# SwitchDemoFeather.net
KiCad netlist of a schematic drawn in EAGLE
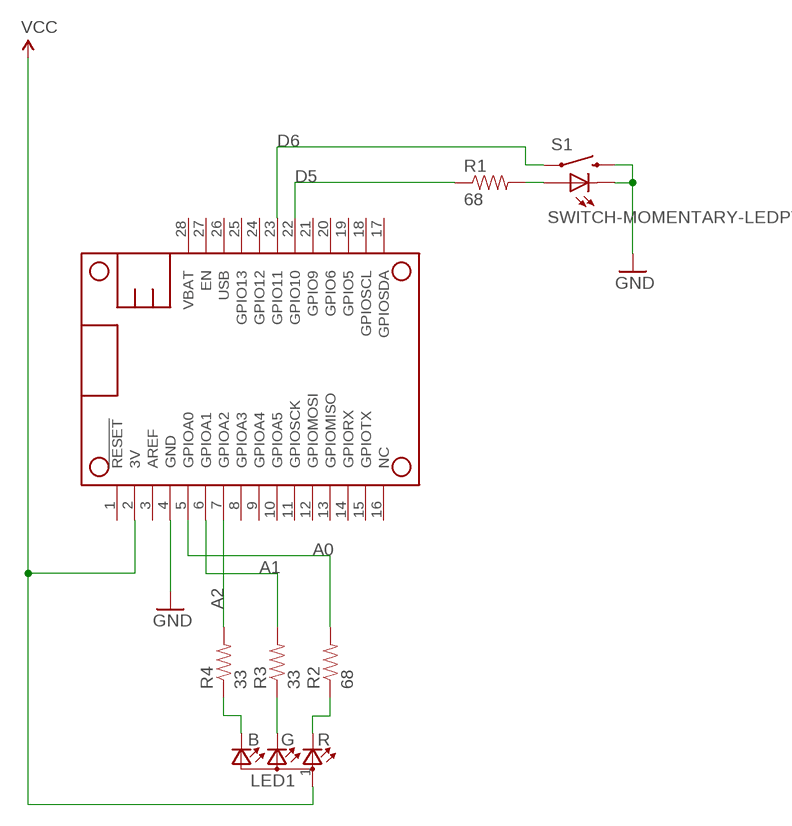
[diagram p0: schematic, sheet 1]

(export (version "E")
  (design (tool "Eeschema 10.0.6"))
  (components
    (comp (ref "LED1")
      (value "LED-RGB-CREE-SMD")
      (footprint "eagle-import:LED-RGB-CREE-SMD")
      (libsource (lib "eagle-import") (part "LED-RGB-CREE-SMD"))
    )
    (comp (ref "MS1")
      (value "FEATHERWING")
      (footprint "eagle-import:FEATHERWING")
      (libsource (lib "eagle-import") (part "FEATHERWING"))
    )
    (comp (ref "R1")
      (value "68")
      (footprint "eagle-import:0603-RES")
      (libsource (lib "eagle-import") (part "RES-68-0603.DEV"))
    )
    (comp (ref "R2")
      (value "68")
      (footprint "eagle-import:0603-RES")
      (libsource (lib "eagle-import") (part "RES-68-0603.DEV"))
    )
    (comp (ref "R3")
      (value "33")
      (footprint "eagle-import:0603-RES")
      (libsource (lib "eagle-import") (part "RES-33-0603.DEV"))
    )
    (comp (ref "R4")
      (value "33")
      (footprint "eagle-import:0603-RES")
      (libsource (lib "eagle-import") (part "RES-33-0603.DEV"))
    )
    (comp (ref "S1")
      (value "SWITCH-MOMENTARY-LEDPTH")
      (footprint "eagle-import:TACTILE-PTH-LED-12MM")
      (libsource (lib "eagle-import") (part "SWITCH-MOMENTARY-LEDPTH"))
    )
  )
  (nets
    (net (code "1") (name "/A0") (class "Default")
      (node (ref "MS1") (pin "5") (pinfunction "GPIOA0_5") (pintype "bidirectional"))
      (node (ref "R2") (pin "2") (pinfunction "2_2") (pintype "passive"))
    )
    (net (code "2") (name "/A1") (class "Default")
      (node (ref "MS1") (pin "6") (pinfunction "GPIOA1_6") (pintype "bidirectional"))
      (node (ref "R3") (pin "2") (pinfunction "2_2") (pintype "passive"))
    )
    (net (code "3") (name "/A2") (class "Default")
      (node (ref "MS1") (pin "7") (pinfunction "GPIOA2_7") (pintype "bidirectional"))
      (node (ref "R4") (pin "2") (pinfunction "2_2") (pintype "passive"))
    )
    (net (code "4") (name "/D5") (class "Default")
      (node (ref "MS1") (pin "22") (pinfunction "GPIO10_22") (pintype "bidirectional"))
      (node (ref "R1") (pin "1") (pinfunction "1_1") (pintype "passive"))
    )
    (net (code "5") (name "/D6") (class "Default")
      (node (ref "MS1") (pin "23") (pinfunction "GPIO11_23") (pintype "bidirectional"))
      (node (ref "S1") (pin "4") (pinfunction "1_4") (pintype "passive"))
    )
    (net (code "6") (name "/USB") (class "Default")
      (node (ref "MS1") (pin "26") (pinfunction "USB_26") (pintype "power_in"))
    )
    (net (code "7") (name "/VBAT") (class "Default")
      (node (ref "MS1") (pin "28") (pinfunction "VBAT_28") (pintype "power_in"))
    )
    (net (code "8") (name "GND") (class "Default")
      (node (ref "MS1") (pin "4") (pinfunction "GND_4") (pintype "power_in"))
      (node (ref "S1") (pin "2") (pinfunction "2_2") (pintype "passive"))
      (node (ref "S1") (pin "C") (pinfunction "C_C") (pintype "passive"))
    )
    (net (code "9") (name "Net-(LED1-B)") (class "Default")
      (node (ref "LED1") (pin "2") (pinfunction "B_2") (pintype "passive"))
      (node (ref "R4") (pin "1") (pinfunction "1_1") (pintype "passive"))
    )
    (net (code "10") (name "Net-(LED1-G)") (class "Default")
      (node (ref "LED1") (pin "3") (pinfunction "G_3") (pintype "passive"))
      (node (ref "R3") (pin "1") (pinfunction "1_1") (pintype "passive"))
    )
    (net (code "11") (name "Net-(LED1-R)") (class "Default")
      (node (ref "LED1") (pin "4") (pinfunction "R_4") (pintype "passive"))
      (node (ref "R2") (pin "1") (pinfunction "1_1") (pintype "passive"))
    )
    (net (code "12") (name "Net-(R1-Pad2)") (class "Default")
      (node (ref "R1") (pin "2") (pinfunction "2_2") (pintype "passive"))
      (node (ref "S1") (pin "A") (pinfunction "A_A") (pintype "passive"))
    )
    (net (code "13") (name "VCC") (class "Default")
      (node (ref "LED1") (pin "1") (pinfunction "A_1") (pintype "passive"))
      (node (ref "MS1") (pin "2") (pinfunction "3V_2") (pintype "power_in"))
    )
    (net (code "14") (name "unconnected-(MS1-AREF-Pad3)") (class "Default")
      (node (ref "MS1") (pin "3") (pinfunction "AREF_3") (pintype "passive"))
    )
    (net (code "15") (name "unconnected-(MS1-EN-Pad27)") (class "Default")
      (node (ref "MS1") (pin "27") (pinfunction "EN_27") (pintype "passive"))
    )
    (net (code "16") (name "unconnected-(MS1-GPIO5-Pad19)") (class "Default")
      (node (ref "MS1") (pin "19") (pinfunction "GPIO5_19") (pintype "bidirectional"))
    )
    (net (code "17") (name "unconnected-(MS1-GPIO6-Pad20)") (class "Default")
      (node (ref "MS1") (pin "20") (pinfunction "GPIO6_20") (pintype "bidirectional"))
    )
    (net (code "18") (name "unconnected-(MS1-GPIO9-Pad21)") (class "Default")
      (node (ref "MS1") (pin "21") (pinfunction "GPIO9_21") (pintype "bidirectional"))
    )
    (net (code "19") (name "unconnected-(MS1-GPIO12-Pad24)") (class "Default")
      (node (ref "MS1") (pin "24") (pinfunction "GPIO12_24") (pintype "bidirectional"))
    )
    (net (code "20") (name "unconnected-(MS1-GPIO13-Pad25)") (class "Default")
      (node (ref "MS1") (pin "25") (pinfunction "GPIO13_25") (pintype "bidirectional"))
    )
    (net (code "21") (name "unconnected-(MS1-GPIOA3-Pad8)") (class "Default")
      (node (ref "MS1") (pin "8") (pinfunction "GPIOA3_8") (pintype "bidirectional"))
    )
    (net (code "22") (name "unconnected-(MS1-GPIOA4-Pad9)") (class "Default")
      (node (ref "MS1") (pin "9") (pinfunction "GPIOA4_9") (pintype "bidirectional"))
    )
    (net (code "23") (name "unconnected-(MS1-GPIOA5-Pad10)") (class "Default")
      (node (ref "MS1") (pin "10") (pinfunction "GPIOA5_10") (pintype "bidirectional"))
    )
    (net (code "24") (name "unconnected-(MS1-GPIOMISO-Pad13)") (class "Default")
      (node (ref "MS1") (pin "13") (pinfunction "GPIOMISO_13") (pintype "bidirectional"))
    )
    (net (code "25") (name "unconnected-(MS1-GPIOMOSI-Pad12)") (class "Default")
      (node (ref "MS1") (pin "12") (pinfunction "GPIOMOSI_12") (pintype "bidirectional"))
    )
    (net (code "26") (name "unconnected-(MS1-GPIORX-Pad14)") (class "Default")
      (node (ref "MS1") (pin "14") (pinfunction "GPIORX_14") (pintype "bidirectional"))
    )
    (net (code "27") (name "unconnected-(MS1-GPIOSCK-Pad11)") (class "Default")
      (node (ref "MS1") (pin "11") (pinfunction "GPIOSCK_11") (pintype "bidirectional"))
    )
    (net (code "28") (name "unconnected-(MS1-GPIOSCL-Pad18)") (class "Default")
      (node (ref "MS1") (pin "18") (pinfunction "GPIOSCL_18") (pintype "bidirectional"))
    )
    (net (code "29") (name "unconnected-(MS1-GPIOSDA-Pad17)") (class "Default")
      (node (ref "MS1") (pin "17") (pinfunction "GPIOSDA_17") (pintype "bidirectional"))
    )
    (net (code "30") (name "unconnected-(MS1-GPIOTX-Pad15)") (class "Default")
      (node (ref "MS1") (pin "15") (pinfunction "GPIOTX_15") (pintype "bidirectional"))
    )
    (net (code "31") (name "unconnected-(MS1-NC-Pad16)") (class "Default")
      (node (ref "MS1") (pin "16") (pinfunction "NC_16") (pintype "passive"))
    )
    (net (code "32") (name "unconnected-(MS1-~{RESET}-Pad1)") (class "Default")
      (node (ref "MS1") (pin "1") (pinfunction "~{RESET}_1") (pintype "input"))
    )
  )
)
